# 20241014.net
KiCad netlist of a schematic drawn in EasyEDA Pro
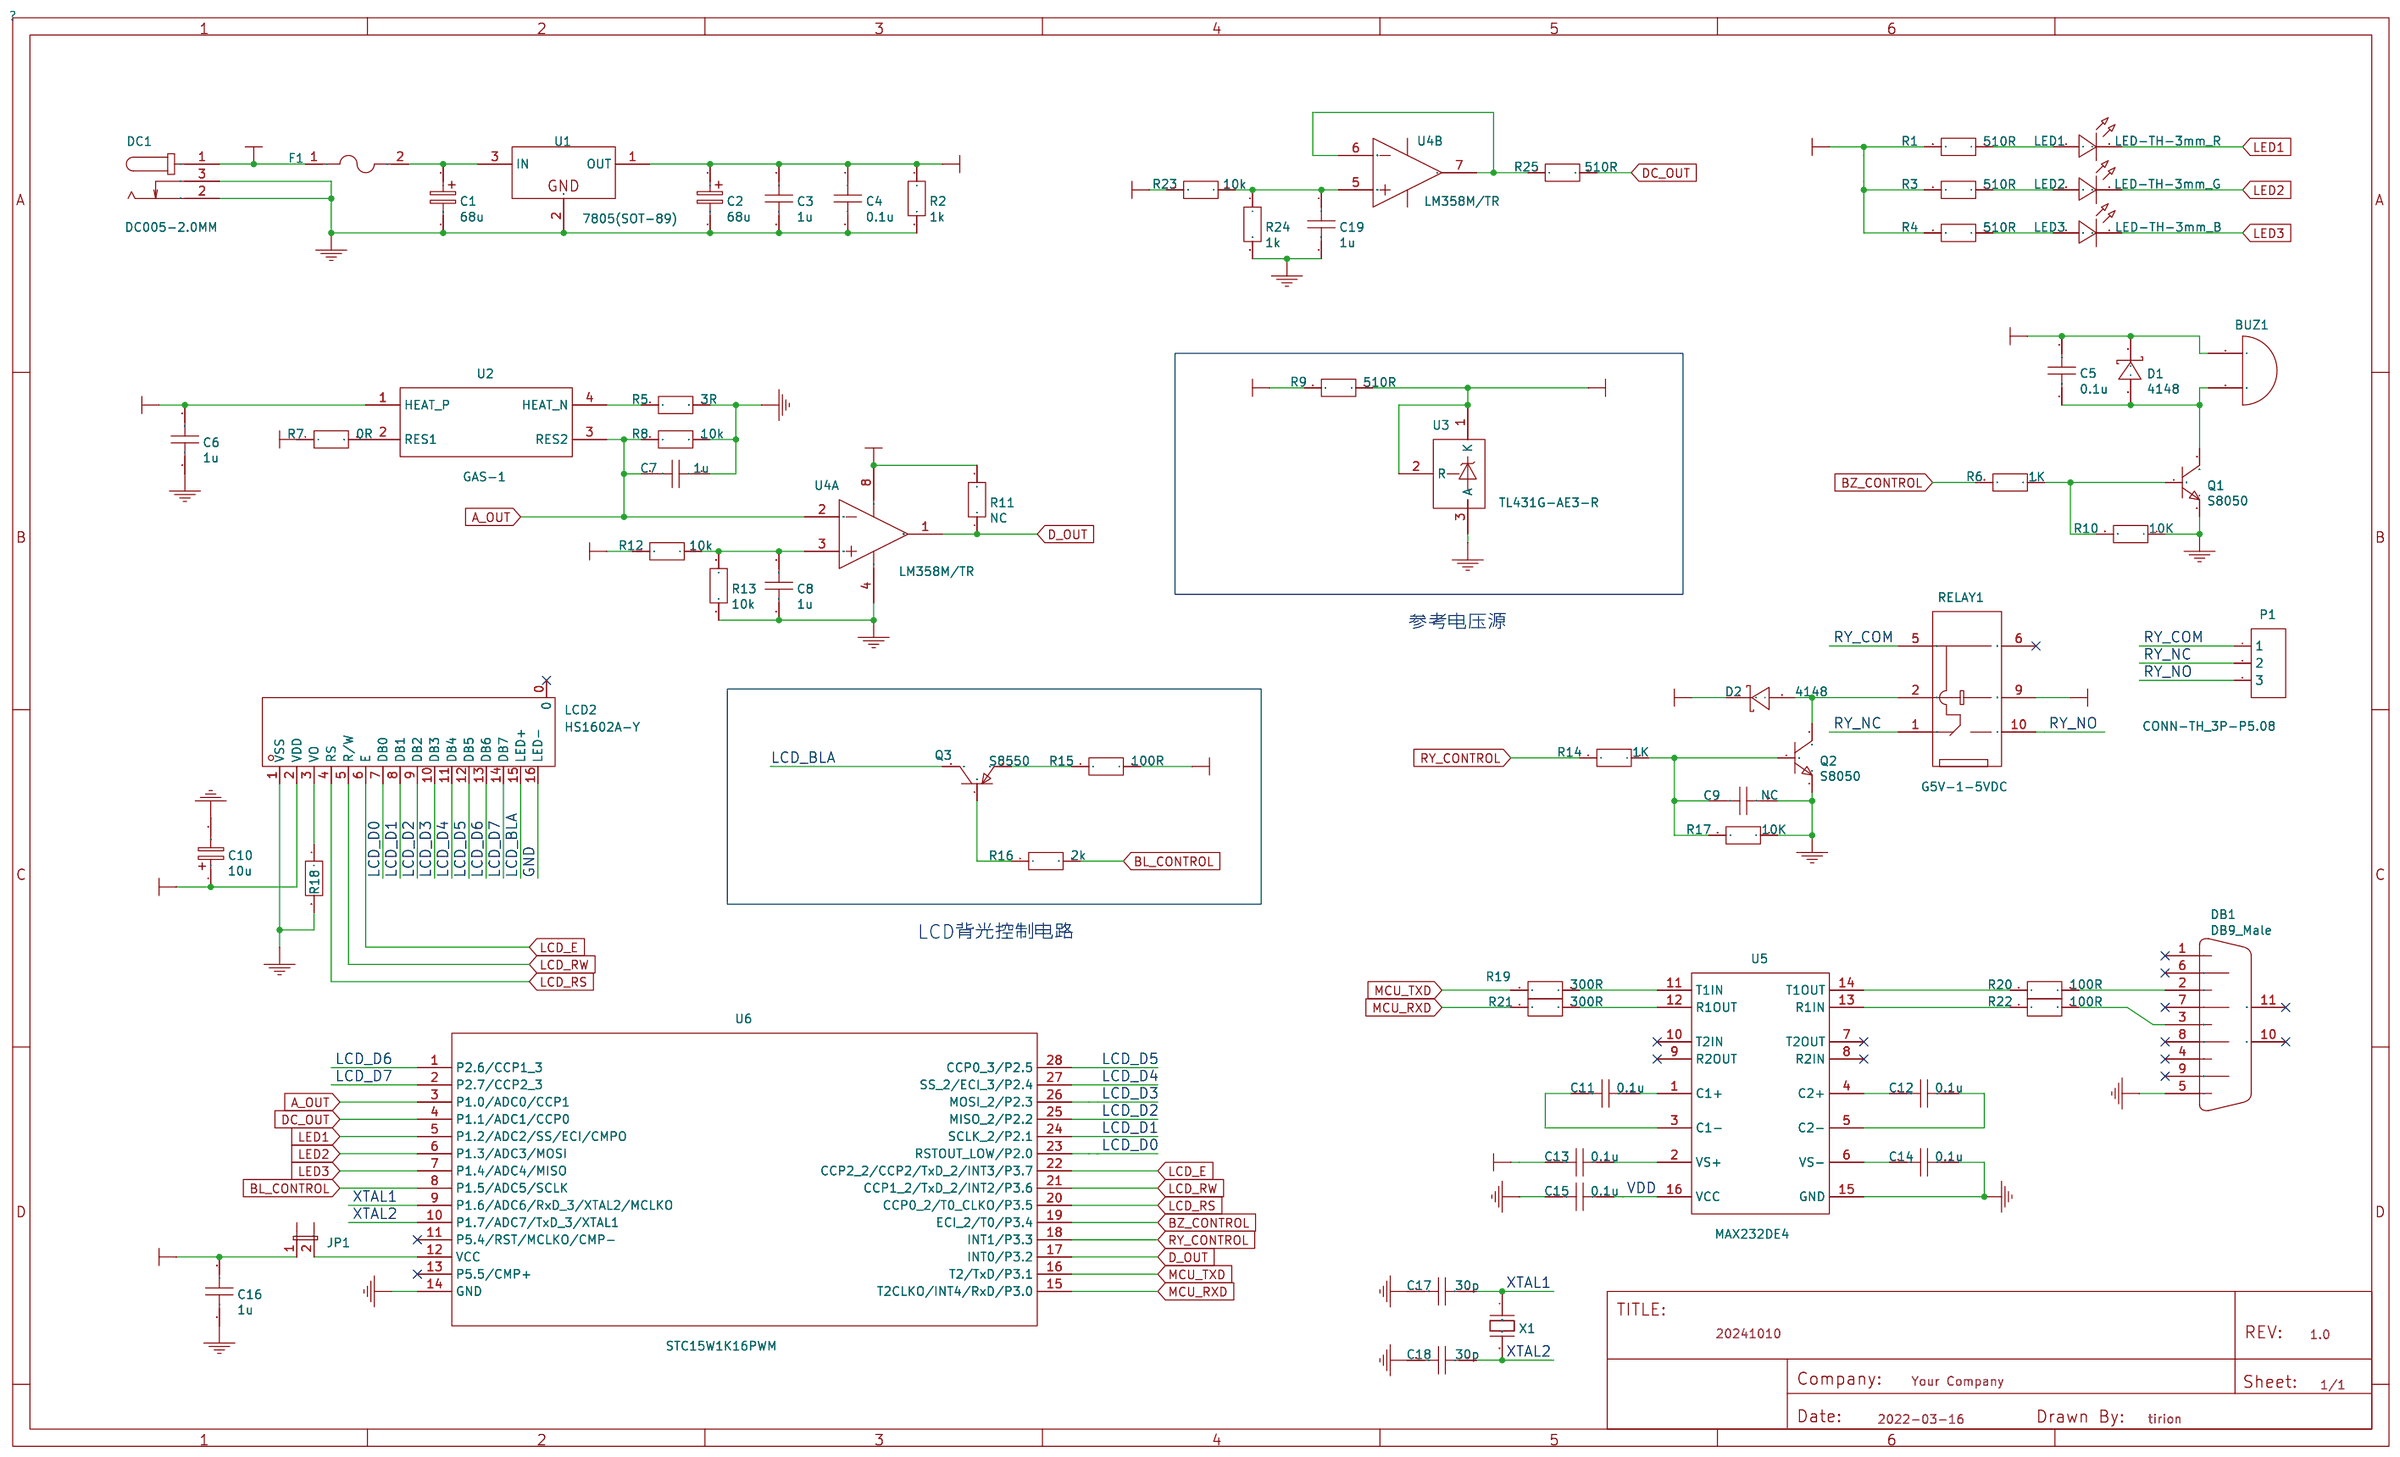
[diagram p0: schematic sheet]

(export (version "E")
  (design (tool "Eeschema 10.0.6"))
  (components
    (comp (ref "BUZ1") (value "BUZ1") (libsource (lib "easyedapro") (part "BUZ1")))
    (comp (ref "C1") (value "68u") (libsource (lib "easyedapro") (part "68u")))
    (comp (ref "C2") (value "68u") (libsource (lib "easyedapro") (part "68u")))
    (comp (ref "C3") (value "1u") (libsource (lib "easyedapro") (part "1u")))
    (comp (ref "C4") (value "0.1u") (libsource (lib "easyedapro") (part "0.1u")))
    (comp (ref "C5") (value "0.1u") (libsource (lib "easyedapro") (part "0.1u")))
    (comp (ref "C6") (value "1u") (libsource (lib "easyedapro") (part "1u")))
    (comp (ref "C7") (value "1u") (libsource (lib "easyedapro") (part "1u")))
    (comp (ref "C8") (value "1u") (libsource (lib "easyedapro") (part "1u")))
    (comp (ref "C9") (value "NC") (libsource (lib "easyedapro") (part "NC")))
    (comp (ref "C10") (value "10u") (libsource (lib "easyedapro") (part "10u")))
    (comp (ref "C11") (value "0.1u") (libsource (lib "easyedapro") (part "0.1u")))
    (comp (ref "C12") (value "0.1u") (libsource (lib "easyedapro") (part "0.1u")))
    (comp (ref "C13") (value "0.1u") (libsource (lib "easyedapro") (part "0.1u")))
    (comp (ref "C14") (value "0.1u") (libsource (lib "easyedapro") (part "0.1u")))
    (comp (ref "C15") (value "0.1u") (libsource (lib "easyedapro") (part "0.1u")))
    (comp (ref "C16") (value "1u") (libsource (lib "easyedapro") (part "1u")))
    (comp (ref "C17") (value "30p") (libsource (lib "easyedapro") (part "30p")))
    (comp (ref "C18") (value "30p") (libsource (lib "easyedapro") (part "30p")))
    (comp (ref "C19") (value "1u") (libsource (lib "easyedapro") (part "1u")))
    (comp (ref "D1")
      (value "4148")
      (fields (field (name "Manufacturer Part") "SS14") (field (name "Manufacturer") "MDD"))
      (libsource (lib "easyedapro") (part "4148"))
    )
    (comp (ref "D2")
      (value "4148")
      (fields (field (name "Manufacturer Part") "SS14") (field (name "Manufacturer") "MDD"))
      (libsource (lib "easyedapro") (part "4148"))
    )
    (comp (ref "DB1")
      (value "DB9_Male")
      (fields (field (name "Manufacturer") "Amphenol"))
      (libsource (lib "easyedapro") (part "DB9_Male"))
    )
    (comp (ref "DC1")
      (value "DC005-2.0MM")
      (fields (field (name "Manufacturer") "SOFNG"))
      (libsource (lib "easyedapro") (part "DC005-2.0MM"))
    )
    (comp (ref "F1") (value "FUSE_F1812_FUSE") (libsource (lib "easyedapro") (part "FUSE_F1812_FUSE")))
    (comp (ref "JP1") (value "JUMPER2") (libsource (lib "easyedapro") (part "JUMPER2")))
    (comp (ref "LCD2")
      (value "HS1602A-Y")
      (footprint "easyedapro:LCD1602")
      (description "主控芯片:SPLC780;尺寸(inch):2;")
      (fields (field (name "Manufacturer") "HS(汉昇)"))
      (libsource (lib "easyedapro") (part "HS1602A-Y"))
    )
    (comp (ref "LED1")
      (value "LED-TH-3mm_R")
      (fields
        (field (name "Manufacturer Part") "204-10SDRD/S530-A3-L")
        (field (name "Manufacturer") "EVERLIGHT(台湾亿光)")
      )
      (libsource (lib "easyedapro") (part "LED-TH-3mm_R"))
    )
    (comp (ref "LED2")
      (value "LED-TH-3mm_G")
      (fields
        (field (name "Manufacturer Part") "204-10SYGD/S530-E3")
        (field (name "Manufacturer") "EVERLIGHT(台湾亿光)")
      )
      (libsource (lib "easyedapro") (part "LED-TH-3mm_G"))
    )
    (comp (ref "LED3")
      (value "LED-TH-3mm_B")
      (fields
        (field (name "Manufacturer Part") "204-10SUBC/S400-A4")
        (field (name "Manufacturer") "EVERLIGHT(台湾亿光)")
      )
      (libsource (lib "easyedapro") (part "LED-TH-3mm_B"))
    )
    (comp (ref "P1") (value "CONN-TH_3P-P5.08") (libsource (lib "easyedapro") (part "CONN-TH_3P-P5.08")))
    (comp (ref "Q1")
      (value "S8050")
      (fields (field (name "Manufacturer") "JSMSEMI"))
      (libsource (lib "easyedapro") (part "S8050"))
    )
    (comp (ref "Q2")
      (value "S8050")
      (fields (field (name "Manufacturer") "JSMSEMI"))
      (libsource (lib "easyedapro") (part "S8050"))
    )
    (comp (ref "Q3")
      (value "S8550")
      (fields
        (field (name "Manufacturer Part") "S8550-H")
        (field (name "Manufacturer") "Yangzhou Yangjie Elec Tech")
      )
      (libsource (lib "easyedapro") (part "S8550"))
    )
    (comp (ref "R1") (value "510R") (libsource (lib "easyedapro") (part "510R")))
    (comp (ref "R2") (value "1k") (libsource (lib "easyedapro") (part "1k")))
    (comp (ref "R3") (value "510R") (libsource (lib "easyedapro") (part "510R")))
    (comp (ref "R4") (value "510R") (libsource (lib "easyedapro") (part "510R")))
    (comp (ref "R5") (value "3R") (libsource (lib "easyedapro") (part "3R")))
    (comp (ref "R6") (value "1K") (libsource (lib "easyedapro") (part "1K")))
    (comp (ref "R7") (value "0R") (libsource (lib "easyedapro") (part "0R")))
    (comp (ref "R8") (value "10k") (libsource (lib "easyedapro") (part "10k")))
    (comp (ref "R9") (value "510R") (libsource (lib "easyedapro") (part "510R")))
    (comp (ref "R10") (value "10K") (libsource (lib "easyedapro") (part "10K")))
    (comp (ref "R11") (value "NC") (libsource (lib "") (part "NC_1")))
    (comp (ref "R12") (value "10k") (libsource (lib "easyedapro") (part "10k")))
    (comp (ref "R13") (value "10k") (libsource (lib "easyedapro") (part "10k")))
    (comp (ref "R14") (value "1K") (libsource (lib "easyedapro") (part "1K")))
    (comp (ref "R15") (value "100R") (libsource (lib "easyedapro") (part "100R")))
    (comp (ref "R16") (value "2k") (libsource (lib "easyedapro") (part "2k")))
    (comp (ref "R17") (value "10K") (libsource (lib "easyedapro") (part "10K")))
    (comp (ref "R18") (value "10k") (libsource (lib "easyedapro") (part "10k")))
    (comp (ref "R19") (value "300R") (libsource (lib "easyedapro") (part "300R")))
    (comp (ref "R20") (value "100R") (libsource (lib "easyedapro") (part "100R")))
    (comp (ref "R21") (value "300R") (libsource (lib "easyedapro") (part "300R")))
    (comp (ref "R22") (value "100R") (libsource (lib "easyedapro") (part "100R")))
    (comp (ref "R23") (value "10k") (libsource (lib "easyedapro") (part "10k")))
    (comp (ref "R24") (value "1k") (libsource (lib "easyedapro") (part "1k")))
    (comp (ref "R25") (value "510R") (libsource (lib "easyedapro") (part "510R")))
    (comp (ref "RELAY1")
      (value "G5V-1-5VDC")
      (fields (field (name "Manufacturer") "OMRON"))
      (libsource (lib "easyedapro") (part "G5V-1-5VDC"))
    )
    (comp (ref "U1")
      (value "7805(SOT-89)")
      (fields (field (name "Manufacturer Part") "CJ78L05") (field (name "Manufacturer") "CJ"))
      (libsource (lib "easyedapro") (part "7805(SOT-89)"))
    )
    (comp (ref "U2") (value "GAS-1") (libsource (lib "easyedapro") (part "GAS-1")))
    (comp (ref "U3")
      (value "TL431G-AE3-R")
      (fields (field (name "Manufacturer") "UTC"))
      (libsource (lib "easyedapro") (part "TL431G-AE3-R"))
    )
    (comp (ref "U4")
      (value "LM358M/TR")
      (fields (field (name "Manufacturer") "HGSEMI"))
      (libsource (lib "easyedapro") (part "LM358M/TR"))
    )
    (comp (ref "U5") (value "MAX232DE4") (libsource (lib "easyedapro") (part "MAX232DE4")))
    (comp (ref "U6")
      (value "STC15W1K16PWM")
      (fields (field (name "Manufacturer") "STC"))
      (libsource (lib "easyedapro") (part "STC15W1K16PWM"))
    )
    (comp (ref "X1")
      (value "12MHZ")
      (fields (field (name "Manufacturer Part") "X49UD12MSD2SC") (field (name "Manufacturer") "LCSC"))
      (libsource (lib "easyedapro") (part "12MHZ"))
    )
  )
  (nets
    (net (code "1") (name "/LCD_BLA") (class "Default")
      (node (ref "LCD2") (pin "15") (pinfunction "LED+_15") (pintype "unspecified"))
      (node (ref "Q3") (pin "3") (pinfunction "C_3") (pintype "input"))
    )
    (net (code "2") (name "/LCD_D0") (class "Default")
      (node (ref "LCD2") (pin "7") (pinfunction "DB0_7") (pintype "unspecified"))
      (node (ref "U6") (pin "23") (pinfunction "RSTOUT_LOW/P2.0_23") (pintype "unspecified"))
    )
    (net (code "3") (name "/LCD_D1") (class "Default")
      (node (ref "LCD2") (pin "8") (pinfunction "DB1_8") (pintype "unspecified"))
      (node (ref "U6") (pin "24") (pinfunction "SCLK_2/P2.1_24") (pintype "unspecified"))
    )
    (net (code "4") (name "/LCD_D2") (class "Default")
      (node (ref "LCD2") (pin "9") (pinfunction "DB2_9") (pintype "unspecified"))
      (node (ref "U6") (pin "25") (pinfunction "MISO_2/P2.2_25") (pintype "unspecified"))
    )
    (net (code "5") (name "/LCD_D3") (class "Default")
      (node (ref "LCD2") (pin "10") (pinfunction "DB3_10") (pintype "unspecified"))
      (node (ref "U6") (pin "26") (pinfunction "MOSI_2/P2.3_26") (pintype "unspecified"))
    )
    (net (code "6") (name "/LCD_D4") (class "Default")
      (node (ref "LCD2") (pin "11") (pinfunction "DB4_11") (pintype "unspecified"))
      (node (ref "U6") (pin "27") (pinfunction "SS_2/ECI_3/P2.4_27") (pintype "unspecified"))
    )
    (net (code "7") (name "/LCD_D5") (class "Default")
      (node (ref "LCD2") (pin "12") (pinfunction "DB5_12") (pintype "unspecified"))
      (node (ref "U6") (pin "28") (pinfunction "CCP0_3/P2.5_28") (pintype "unspecified"))
    )
    (net (code "8") (name "/LCD_D6") (class "Default")
      (node (ref "LCD2") (pin "13") (pinfunction "DB6_13") (pintype "unspecified"))
      (node (ref "U6") (pin "1") (pinfunction "P2.6/CCP1_3_1") (pintype "unspecified"))
    )
    (net (code "9") (name "/LCD_D7") (class "Default")
      (node (ref "LCD2") (pin "14") (pinfunction "DB7_14") (pintype "unspecified"))
      (node (ref "U6") (pin "2") (pinfunction "P2.7/CCP2_3_2") (pintype "unspecified"))
    )
    (net (code "10") (name "/RY_COM") (class "Default")
      (node (ref "P1") (pin "1") (pinfunction "1_1") (pintype "unspecified"))
      (node (ref "RELAY1") (pin "5") (pinfunction "5_5") (pintype "input"))
    )
    (net (code "11") (name "/RY_NC") (class "Default")
      (node (ref "P1") (pin "2") (pinfunction "2_2") (pintype "unspecified"))
      (node (ref "RELAY1") (pin "1") (pinfunction "1_1") (pintype "input"))
    )
    (net (code "12") (name "/RY_NO") (class "Default")
      (node (ref "P1") (pin "3") (pinfunction "3_3") (pintype "unspecified"))
      (node (ref "RELAY1") (pin "10") (pinfunction "10_10") (pintype "input"))
    )
    (net (code "13") (name "/XTAL1") (class "Default")
      (node (ref "C17") (pin "1") (pinfunction "1_1") (pintype "unspecified"))
      (node (ref "U6") (pin "9") (pinfunction "P1.6/ADC6/RxD_3/XTAL2/MCLKO_9") (pintype "unspecified"))
      (node (ref "X1") (pin "1") (pinfunction "OSC1_1") (pintype "input"))
    )
    (net (code "14") (name "/XTAL2") (class "Default")
      (node (ref "C18") (pin "1") (pinfunction "1_1") (pintype "unspecified"))
      (node (ref "U6") (pin "10") (pinfunction "P1.7/ADC7/TxD_3/XTAL1_10") (pintype "unspecified"))
      (node (ref "X1") (pin "2") (pinfunction "OSC2_2") (pintype "input"))
    )
    (net (code "15") (name "A_OUT") (class "Default")
      (node (ref "C7") (pin "2") (pinfunction "2_2") (pintype "unspecified"))
      (node (ref "R8") (pin "1") (pinfunction "1_1") (pintype "unspecified"))
      (node (ref "U2") (pin "3") (pinfunction "RES2_3") (pintype "unspecified"))
      (node (ref "U4") (pin "2") (pinfunction "1IN-_2") (pintype "unspecified"))
      (node (ref "U6") (pin "3") (pinfunction "P1.0/ADC0/CCP1_3") (pintype "unspecified"))
    )
    (net (code "16") (name "BL_CONTROL") (class "Default")
      (node (ref "R16") (pin "2") (pinfunction "2_2") (pintype "unspecified"))
      (node (ref "U6") (pin "8") (pinfunction "P1.5/ADC5/SCLK_8") (pintype "unspecified"))
    )
    (net (code "17") (name "BZ_CONTROL") (class "Default")
      (node (ref "R6") (pin "2") (pinfunction "2_2") (pintype "unspecified"))
      (node (ref "U6") (pin "19") (pinfunction "ECI_2/T0/P3.4_19") (pintype "unspecified"))
    )
    (net (code "18") (name "DC_IN") (class "Default")
      (node (ref "DC1") (pin "1") (pinfunction "1_1") (pintype "unspecified"))
      (node (ref "F1") (pin "1") (pinfunction "1_1") (pintype "unspecified"))
      (node (ref "R23") (pin "2") (pinfunction "2_2") (pintype "unspecified"))
    )
    (net (code "19") (name "DC_OUT") (class "Default")
      (node (ref "R25") (pin "1") (pinfunction "1_1") (pintype "unspecified"))
      (node (ref "U6") (pin "4") (pinfunction "P1.1/ADC1/CCP0_4") (pintype "unspecified"))
    )
    (net (code "20") (name "D_OUT") (class "Default")
      (node (ref "R11") (pin "1") (pinfunction "1_1") (pintype "unspecified"))
      (node (ref "U4") (pin "1") (pinfunction "1OUT_1") (pintype "output"))
      (node (ref "U6") (pin "17") (pinfunction "INT0/P3.2_17") (pintype "unspecified"))
    )
    (net (code "21") (name "GND") (class "Default")
      (node (ref "C1") (pin "2") (pinfunction "2_2") (pintype "unspecified"))
      (node (ref "C10") (pin "2") (pinfunction "2_2") (pintype "unspecified"))
      (node (ref "C14") (pin "2") (pinfunction "2_2") (pintype "unspecified"))
      (node (ref "C15") (pin "1") (pinfunction "1_1") (pintype "unspecified"))
      (node (ref "C16") (pin "1") (pinfunction "1_1") (pintype "unspecified"))
      (node (ref "C17") (pin "2") (pinfunction "2_2") (pintype "unspecified"))
      (node (ref "C18") (pin "2") (pinfunction "2_2") (pintype "unspecified"))
      (node (ref "C19") (pin "2") (pinfunction "2_2") (pintype "unspecified"))
      (node (ref "C2") (pin "2") (pinfunction "2_2") (pintype "unspecified"))
      (node (ref "C3") (pin "2") (pinfunction "2_2") (pintype "unspecified"))
      (node (ref "C4") (pin "2") (pinfunction "2_2") (pintype "unspecified"))
      (node (ref "C6") (pin "1") (pinfunction "1_1") (pintype "unspecified"))
      (node (ref "C7") (pin "1") (pinfunction "1_1") (pintype "unspecified"))
      (node (ref "C8") (pin "2") (pinfunction "2_2") (pintype "unspecified"))
      (node (ref "C9") (pin "2") (pinfunction "2_2") (pintype "unspecified"))
      (node (ref "DB1") (pin "5") (pinfunction "5_5") (pintype "input"))
      (node (ref "DC1") (pin "2") (pinfunction "2_2") (pintype "unspecified"))
      (node (ref "DC1") (pin "3") (pinfunction "3_3") (pintype "unspecified"))
      (node (ref "LCD2") (pin "1") (pinfunction "VSS_1") (pintype "unspecified"))
      (node (ref "LCD2") (pin "16") (pinfunction "LED-_16") (pintype "unspecified"))
      (node (ref "Q1") (pin "2") (pinfunction "E_2") (pintype "input"))
      (node (ref "Q2") (pin "2") (pinfunction "E_2") (pintype "input"))
      (node (ref "R10") (pin "1") (pinfunction "1_1") (pintype "unspecified"))
      (node (ref "R13") (pin "2") (pinfunction "2_2") (pintype "unspecified"))
      (node (ref "R17") (pin "1") (pinfunction "1_1") (pintype "unspecified"))
      (node (ref "R18") (pin "2") (pinfunction "2_2") (pintype "unspecified"))
      (node (ref "R2") (pin "2") (pinfunction "2_2") (pintype "unspecified"))
      (node (ref "R24") (pin "2") (pinfunction "2_2") (pintype "unspecified"))
      (node (ref "R5") (pin "2") (pinfunction "2_2") (pintype "unspecified"))
      (node (ref "R8") (pin "2") (pinfunction "2_2") (pintype "unspecified"))
      (node (ref "U1") (pin "2") (pinfunction "GND_2") (pintype "unspecified"))
      (node (ref "U3") (pin "3") (pinfunction "A_3") (pintype "unspecified"))
      (node (ref "U4") (pin "4") (pinfunction "GND_4") (pintype "unspecified"))
      (node (ref "U5") (pin "15") (pinfunction "GND_15") (pintype "unspecified"))
      (node (ref "U6") (pin "14") (pinfunction "GND_14") (pintype "unspecified"))
    )
    (net (code "22") (name "LCD_E") (class "Default")
      (node (ref "LCD2") (pin "6") (pinfunction "E_6") (pintype "unspecified"))
      (node (ref "U6") (pin "22") (pinfunction "CCP2_2/CCP2/TxD_2/INT3/P3.7_22") (pintype "unspecified"))
    )
    (net (code "23") (name "LCD_RS") (class "Default")
      (node (ref "LCD2") (pin "4") (pinfunction "RS_4") (pintype "unspecified"))
      (node (ref "U6") (pin "20") (pinfunction "CCP0_2/T0_CLKO/P3.5_20") (pintype "unspecified"))
    )
    (net (code "24") (name "LCD_RW") (class "Default")
      (node (ref "LCD2") (pin "5") (pinfunction "R/W_5") (pintype "unspecified"))
      (node (ref "U6") (pin "21") (pinfunction "CCP1_2/TxD_2/INT2/P3.6_21") (pintype "unspecified"))
    )
    (net (code "25") (name "LED1") (class "Default")
      (node (ref "LED1") (pin "2") (pinfunction "2_2") (pintype "unspecified"))
      (node (ref "U6") (pin "5") (pinfunction "P1.2/ADC2/SS/ECI/CMPO_5") (pintype "unspecified"))
    )
    (net (code "26") (name "LED2") (class "Default")
      (node (ref "LED2") (pin "2") (pinfunction "2_2") (pintype "unspecified"))
      (node (ref "U6") (pin "6") (pinfunction "P1.3/ADC3/MOSI_6") (pintype "unspecified"))
    )
    (net (code "27") (name "LED3") (class "Default")
      (node (ref "LED3") (pin "2") (pinfunction "2_2") (pintype "unspecified"))
      (node (ref "U6") (pin "7") (pinfunction "P1.4/ADC4/MISO_7") (pintype "unspecified"))
    )
    (net (code "28") (name "MCU_RXD") (class "Default")
      (node (ref "R21") (pin "1") (pinfunction "1_1") (pintype "unspecified"))
      (node (ref "U6") (pin "15") (pinfunction "T2CLKO/INT4/RxD/P3.0_15") (pintype "unspecified"))
    )
    (net (code "29") (name "MCU_TXD") (class "Default")
      (node (ref "R19") (pin "1") (pinfunction "1_1") (pintype "unspecified"))
      (node (ref "U6") (pin "16") (pinfunction "T2/TxD/P3.1_16") (pintype "unspecified"))
    )
    (net (code "30") (name "Net-(BUZ1-B)") (class "Default")
      (node (ref "BUZ1") (pin "2") (pinfunction "B_2") (pintype "unspecified"))
      (node (ref "C5") (pin "1") (pinfunction "1_1") (pintype "unspecified"))
      (node (ref "D1") (pin "2") (pinfunction "A_2") (pintype "unspecified"))
      (node (ref "Q1") (pin "3") (pinfunction "C_3") (pintype "input"))
    )
    (net (code "31") (name "Net-(D2-A)") (class "Default")
      (node (ref "D2") (pin "2") (pinfunction "A_2") (pintype "unspecified"))
      (node (ref "Q2") (pin "3") (pinfunction "C_3") (pintype "input"))
      (node (ref "RELAY1") (pin "2") (pinfunction "2_2") (pintype "input"))
    )
    (net (code "32") (name "Net-(DB1-Pad2)") (class "Default")
      (node (ref "DB1") (pin "2") (pinfunction "2_2") (pintype "input"))
      (node (ref "R20") (pin "2") (pinfunction "2_2") (pintype "unspecified"))
    )
    (net (code "33") (name "Net-(DB1-Pad3)") (class "Default")
      (node (ref "DB1") (pin "3") (pinfunction "3_3") (pintype "input"))
      (node (ref "R22") (pin "2") (pinfunction "2_2") (pintype "unspecified"))
    )
    (net (code "34") (name "Net-(LCD2-VO)") (class "Default")
      (node (ref "LCD2") (pin "3") (pinfunction "VO_3") (pintype "unspecified"))
      (node (ref "R18") (pin "1") (pinfunction "1_1") (pintype "unspecified"))
    )
    (net (code "35") (name "Net-(LED1-Pad1)") (class "Default")
      (node (ref "LED1") (pin "1") (pinfunction "1_1") (pintype "unspecified"))
      (node (ref "R1") (pin "1") (pinfunction "1_1") (pintype "unspecified"))
    )
    (net (code "36") (name "Net-(LED2-Pad1)") (class "Default")
      (node (ref "LED2") (pin "1") (pinfunction "1_1") (pintype "unspecified"))
      (node (ref "R3") (pin "1") (pinfunction "1_1") (pintype "unspecified"))
    )
    (net (code "37") (name "Net-(LED3-Pad1)") (class "Default")
      (node (ref "LED3") (pin "1") (pinfunction "1_1") (pintype "unspecified"))
      (node (ref "R4") (pin "1") (pinfunction "1_1") (pintype "unspecified"))
    )
    (net (code "38") (name "Net-(Q1-B)") (class "Default")
      (node (ref "Q1") (pin "1") (pinfunction "B_1") (pintype "input"))
      (node (ref "R10") (pin "2") (pinfunction "2_2") (pintype "unspecified"))
      (node (ref "R6") (pin "1") (pinfunction "1_1") (pintype "unspecified"))
    )
    (net (code "39") (name "Net-(Q2-B)") (class "Default")
      (node (ref "C9") (pin "1") (pinfunction "1_1") (pintype "unspecified"))
      (node (ref "Q2") (pin "1") (pinfunction "B_1") (pintype "input"))
      (node (ref "R14") (pin "1") (pinfunction "1_1") (pintype "unspecified"))
      (node (ref "R17") (pin "2") (pinfunction "2_2") (pintype "unspecified"))
    )
    (net (code "40") (name "Net-(Q3-B)") (class "Default")
      (node (ref "Q3") (pin "1") (pinfunction "B_1") (pintype "input"))
      (node (ref "R16") (pin "1") (pinfunction "1_1") (pintype "unspecified"))
    )
    (net (code "41") (name "Net-(Q3-E)") (class "Default")
      (node (ref "Q3") (pin "2") (pinfunction "E_2") (pintype "input"))
      (node (ref "R15") (pin "1") (pinfunction "1_1") (pintype "unspecified"))
    )
    (net (code "42") (name "Net-(U1-IN)") (class "Default")
      (node (ref "C1") (pin "1") (pinfunction "1_1") (pintype "unspecified"))
      (node (ref "F1") (pin "2") (pinfunction "2_2") (pintype "unspecified"))
      (node (ref "U1") (pin "3") (pinfunction "IN_3") (pintype "unspecified"))
    )
    (net (code "43") (name "Net-(U2-HEAT_N)") (class "Default")
      (node (ref "R5") (pin "1") (pinfunction "1_1") (pintype "unspecified"))
      (node (ref "U2") (pin "4") (pinfunction "HEAT_N_4") (pintype "unspecified"))
    )
    (net (code "44") (name "Net-(U2-RES1)") (class "Default")
      (node (ref "R7") (pin "2") (pinfunction "2_2") (pintype "unspecified"))
      (node (ref "U2") (pin "2") (pinfunction "RES1_2") (pintype "unspecified"))
    )
    (net (code "45") (name "Net-(U4A-1IN+)") (class "Default")
      (node (ref "C8") (pin "1") (pinfunction "1_1") (pintype "unspecified"))
      (node (ref "R12") (pin "1") (pinfunction "1_1") (pintype "unspecified"))
      (node (ref "R13") (pin "1") (pinfunction "1_1") (pintype "unspecified"))
      (node (ref "U4") (pin "3") (pinfunction "1IN+_3") (pintype "unspecified"))
    )
    (net (code "46") (name "Net-(U4B-2IN+)") (class "Default")
      (node (ref "C19") (pin "1") (pinfunction "1_1") (pintype "unspecified"))
      (node (ref "R23") (pin "1") (pinfunction "1_1") (pintype "unspecified"))
      (node (ref "R24") (pin "1") (pinfunction "1_1") (pintype "unspecified"))
      (node (ref "U4") (pin "5") (pinfunction "2IN+_5") (pintype "unspecified"))
    )
    (net (code "47") (name "Net-(U4B-2IN-)") (class "Default")
      (node (ref "R25") (pin "2") (pinfunction "2_2") (pintype "unspecified"))
      (node (ref "U4") (pin "6") (pinfunction "2IN-_6") (pintype "unspecified"))
      (node (ref "U4") (pin "7") (pinfunction "2OUT_7") (pintype "output"))
    )
    (net (code "48") (name "Net-(U5-C1+)") (class "Default")
      (node (ref "C11") (pin "2") (pinfunction "2_2") (pintype "unspecified"))
      (node (ref "U5") (pin "1") (pinfunction "C1+_1") (pintype "unspecified"))
    )
    (net (code "49") (name "Net-(U5-C1-)") (class "Default")
      (node (ref "C11") (pin "1") (pinfunction "1_1") (pintype "unspecified"))
      (node (ref "U5") (pin "3") (pinfunction "C1-_3") (pintype "unspecified"))
    )
    (net (code "50") (name "Net-(U5-C2+)") (class "Default")
      (node (ref "C12") (pin "1") (pinfunction "1_1") (pintype "unspecified"))
      (node (ref "U5") (pin "4") (pinfunction "C2+_4") (pintype "unspecified"))
    )
    (net (code "51") (name "Net-(U5-C2-)") (class "Default")
      (node (ref "C12") (pin "2") (pinfunction "2_2") (pintype "unspecified"))
      (node (ref "U5") (pin "5") (pinfunction "C2-_5") (pintype "unspecified"))
    )
    (net (code "52") (name "Net-(U5-R1IN)") (class "Default")
      (node (ref "R22") (pin "1") (pinfunction "1_1") (pintype "unspecified"))
      (node (ref "U5") (pin "13") (pinfunction "R1IN_13") (pintype "unspecified"))
    )
    (net (code "53") (name "Net-(U5-R1OUT)") (class "Default")
      (node (ref "R21") (pin "2") (pinfunction "2_2") (pintype "unspecified"))
      (node (ref "U5") (pin "12") (pinfunction "R1OUT_12") (pintype "output"))
    )
    (net (code "54") (name "Net-(U5-T1IN)") (class "Default")
      (node (ref "R19") (pin "2") (pinfunction "2_2") (pintype "unspecified"))
      (node (ref "U5") (pin "11") (pinfunction "T1IN_11") (pintype "unspecified"))
    )
    (net (code "55") (name "Net-(U5-T1OUT)") (class "Default")
      (node (ref "R20") (pin "1") (pinfunction "1_1") (pintype "unspecified"))
      (node (ref "U5") (pin "14") (pinfunction "T1OUT_14") (pintype "output"))
    )
    (net (code "56") (name "Net-(U5-VS+)") (class "Default")
      (node (ref "C13") (pin "2") (pinfunction "2_2") (pintype "unspecified"))
      (node (ref "U5") (pin "2") (pinfunction "VS+_2") (pintype "unspecified"))
    )
    (net (code "57") (name "Net-(U5-VS-)") (class "Default")
      (node (ref "C14") (pin "1") (pinfunction "1_1") (pintype "unspecified"))
      (node (ref "U5") (pin "6") (pinfunction "VS-_6") (pintype "unspecified"))
    )
    (net (code "58") (name "Net-(U6-VCC)") (class "Default")
      (node (ref "JP1") (pin "2") (pinfunction "2_2") (pintype "unspecified"))
      (node (ref "U6") (pin "12") (pinfunction "VCC_12") (pintype "unspecified"))
    )
    (net (code "59") (name "RY_CONTROL") (class "Default")
      (node (ref "R14") (pin "2") (pinfunction "2_2") (pintype "unspecified"))
      (node (ref "U6") (pin "18") (pinfunction "INT1/P3.3_18") (pintype "unspecified"))
    )
    (net (code "60") (name "VDD") (class "Default")
      (node (ref "BUZ1") (pin "1") (pinfunction "A_1") (pintype "unspecified"))
      (node (ref "C10") (pin "1") (pinfunction "1_1") (pintype "unspecified"))
      (node (ref "C13") (pin "1") (pinfunction "1_1") (pintype "unspecified"))
      (node (ref "C15") (pin "2") (pinfunction "2_2") (pintype "unspecified"))
      (node (ref "C16") (pin "2") (pinfunction "2_2") (pintype "unspecified"))
      (node (ref "C2") (pin "1") (pinfunction "1_1") (pintype "unspecified"))
      (node (ref "C3") (pin "1") (pinfunction "1_1") (pintype "unspecified"))
      (node (ref "C4") (pin "1") (pinfunction "1_1") (pintype "unspecified"))
      (node (ref "C5") (pin "2") (pinfunction "2_2") (pintype "unspecified"))
      (node (ref "C6") (pin "2") (pinfunction "2_2") (pintype "unspecified"))
      (node (ref "D1") (pin "1") (pinfunction "K_1") (pintype "unspecified"))
      (node (ref "D2") (pin "1") (pinfunction "K_1") (pintype "unspecified"))
      (node (ref "JP1") (pin "1") (pinfunction "1_1") (pintype "unspecified"))
      (node (ref "LCD2") (pin "2") (pinfunction "VDD_2") (pintype "unspecified"))
      (node (ref "R1") (pin "2") (pinfunction "2_2") (pintype "unspecified"))
      (node (ref "R11") (pin "2") (pinfunction "2_2") (pintype "unspecified"))
      (node (ref "R15") (pin "2") (pinfunction "2_2") (pintype "unspecified"))
      (node (ref "R2") (pin "1") (pinfunction "1_1") (pintype "unspecified"))
      (node (ref "R3") (pin "2") (pinfunction "2_2") (pintype "unspecified"))
      (node (ref "R4") (pin "2") (pinfunction "2_2") (pintype "unspecified"))
      (node (ref "R9") (pin "2") (pinfunction "2_2") (pintype "unspecified"))
      (node (ref "RELAY1") (pin "9") (pinfunction "9_9") (pintype "input"))
      (node (ref "U1") (pin "1") (pinfunction "OUT_1") (pintype "unspecified"))
      (node (ref "U2") (pin "1") (pinfunction "HEAT_P_1") (pintype "unspecified"))
      (node (ref "U4") (pin "8") (pinfunction "VCC_8") (pintype "unspecified"))
      (node (ref "U5") (pin "16") (pinfunction "VCC_16") (pintype "unspecified"))
    )
    (net (code "61") (name "VREF") (class "Default")
      (node (ref "R12") (pin "2") (pinfunction "2_2") (pintype "unspecified"))
      (node (ref "R7") (pin "1") (pinfunction "1_1") (pintype "unspecified"))
      (node (ref "R9") (pin "1") (pinfunction "1_1") (pintype "unspecified"))
      (node (ref "U3") (pin "1") (pinfunction "K_1") (pintype "unspecified"))
      (node (ref "U3") (pin "2") (pinfunction "R_2") (pintype "unspecified"))
    )
    (net (code "62") (name "unconnected-(DB1-MH1-Pad10)") (class "Default")
      (node (ref "DB1") (pin "10") (pinfunction "MH1_10") (pintype "input+no_connect"))
    )
    (net (code "63") (name "unconnected-(DB1-MH2-Pad11)") (class "Default")
      (node (ref "DB1") (pin "11") (pinfunction "MH2_11") (pintype "input+no_connect"))
    )
    (net (code "64") (name "unconnected-(DB1-Pad1)") (class "Default")
      (node (ref "DB1") (pin "1") (pinfunction "1_1") (pintype "input+no_connect"))
    )
    (net (code "65") (name "unconnected-(DB1-Pad4)") (class "Default")
      (node (ref "DB1") (pin "4") (pinfunction "4_4") (pintype "input+no_connect"))
    )
    (net (code "66") (name "unconnected-(DB1-Pad6)") (class "Default")
      (node (ref "DB1") (pin "6") (pinfunction "6_6") (pintype "input+no_connect"))
    )
    (net (code "67") (name "unconnected-(DB1-Pad7)") (class "Default")
      (node (ref "DB1") (pin "7") (pinfunction "7_7") (pintype "input+no_connect"))
    )
    (net (code "68") (name "unconnected-(DB1-Pad8)") (class "Default")
      (node (ref "DB1") (pin "8") (pinfunction "8_8") (pintype "input+no_connect"))
    )
    (net (code "69") (name "unconnected-(DB1-Pad9)") (class "Default")
      (node (ref "DB1") (pin "9") (pinfunction "9_9") (pintype "input+no_connect"))
    )
    (net (code "70") (name "unconnected-(LCD2-Pad0)") (class "Default")
      (node (ref "LCD2") (pin "0") (pinfunction "0_0") (pintype "unspecified+no_connect"))
    )
    (net (code "71") (name "unconnected-(RELAY1-Pad6)") (class "Default")
      (node (ref "RELAY1") (pin "6") (pinfunction "6_6") (pintype "input+no_connect"))
    )
    (net (code "72") (name "unconnected-(U5-R2IN-Pad8)") (class "Default")
      (node (ref "U5") (pin "8") (pinfunction "R2IN_8") (pintype "unspecified+no_connect"))
    )
    (net (code "73") (name "unconnected-(U5-R2OUT-Pad9)") (class "Default")
      (node (ref "U5") (pin "9") (pinfunction "R2OUT_9") (pintype "output+no_connect"))
    )
    (net (code "74") (name "unconnected-(U5-T2IN-Pad10)") (class "Default")
      (node (ref "U5") (pin "10") (pinfunction "T2IN_10") (pintype "unspecified+no_connect"))
    )
    (net (code "75") (name "unconnected-(U5-T2OUT-Pad7)") (class "Default")
      (node (ref "U5") (pin "7") (pinfunction "T2OUT_7") (pintype "output+no_connect"))
    )
    (net (code "76") (name "unconnected-(U6-P5.4{slash}RST{slash}MCLKO{slash}CMP--Pad11)") (class "Default")
      (node (ref "U6") (pin "11") (pinfunction "P5.4/RST/MCLKO/CMP-_11") (pintype "unspecified+no_connect"))
    )
    (net (code "77") (name "unconnected-(U6-P5.5{slash}CMP+-Pad13)") (class "Default")
      (node (ref "U6") (pin "13") (pinfunction "P5.5/CMP+_13") (pintype "unspecified+no_connect"))
    )
  )
)
